# R7FS5D37A3A01CFM.net
KiCad netlist of a schematic drawn in EAGLE
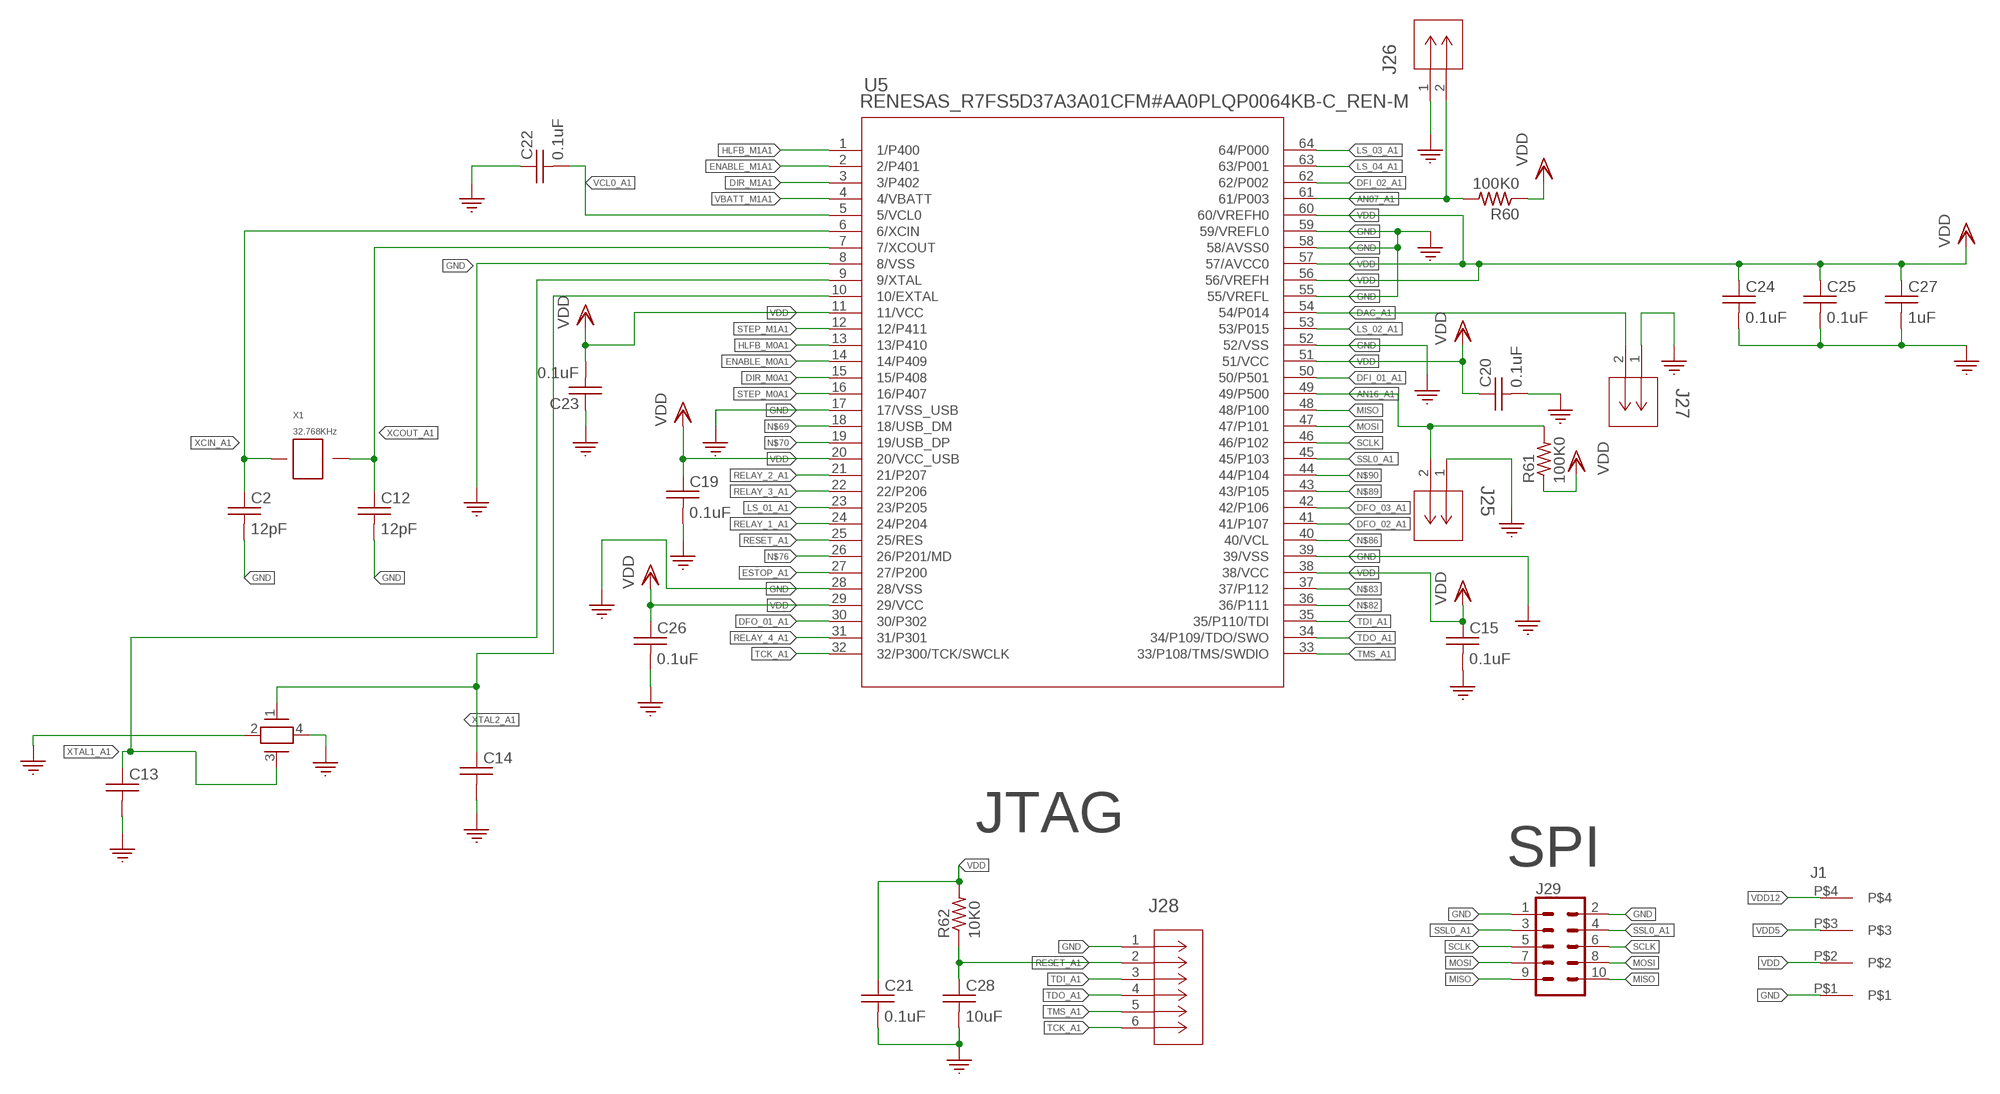
[diagram p0: schematic, sheet 1, part 1 of 3]
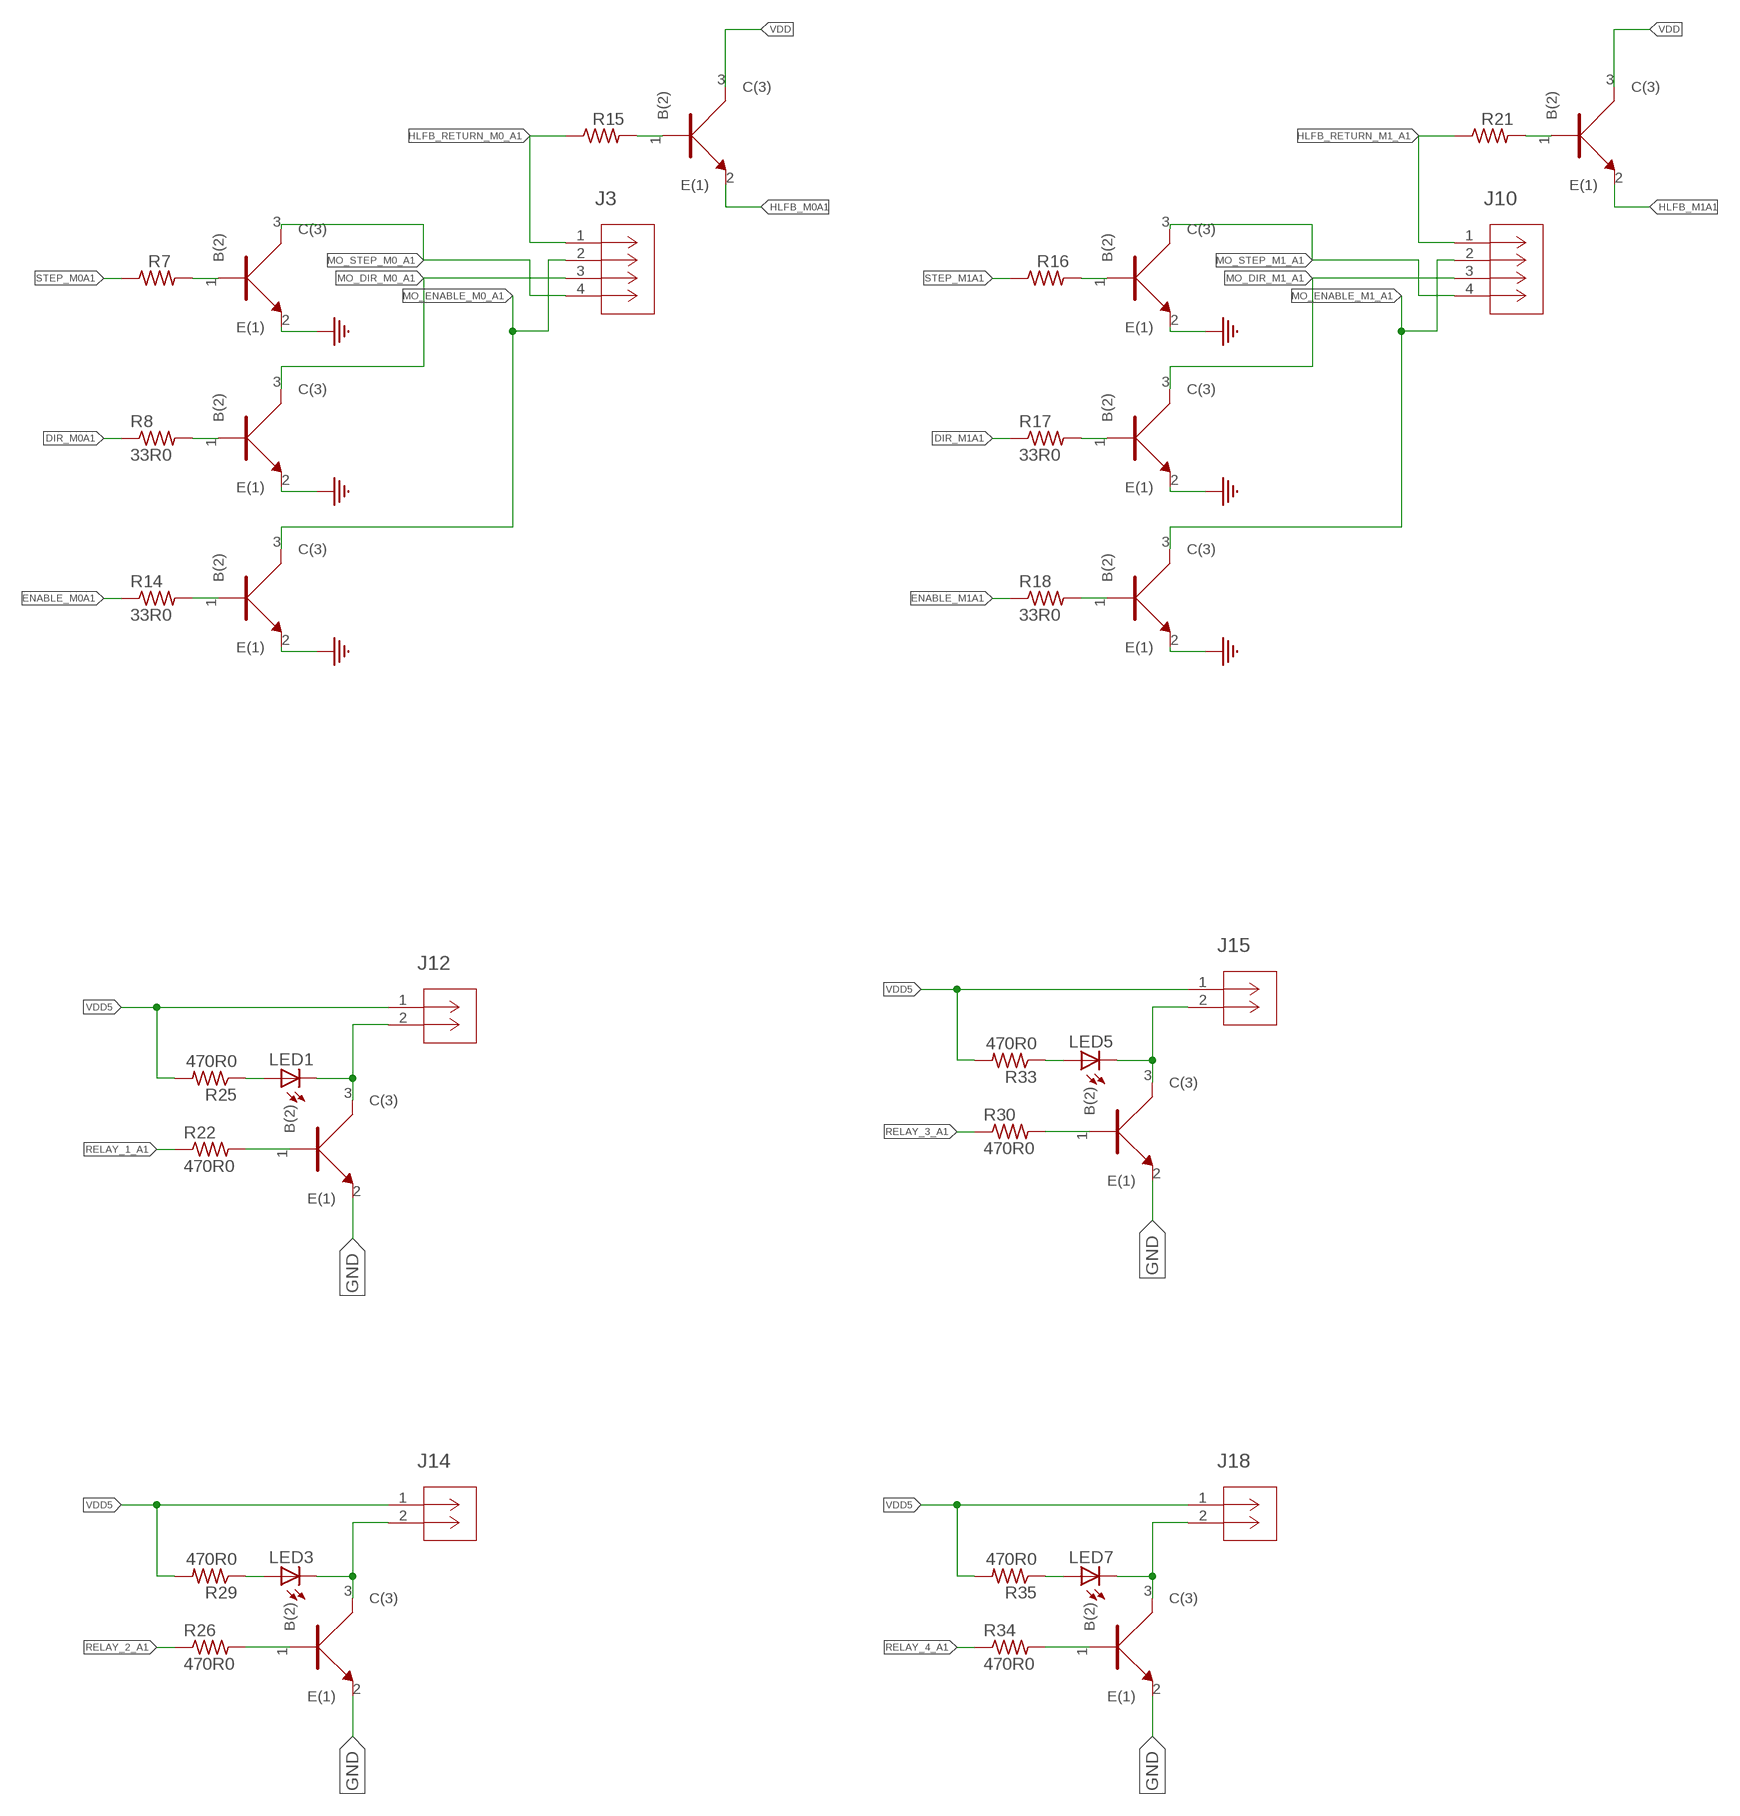
[diagram p1: schematic, sheet 1, part 2 of 3]
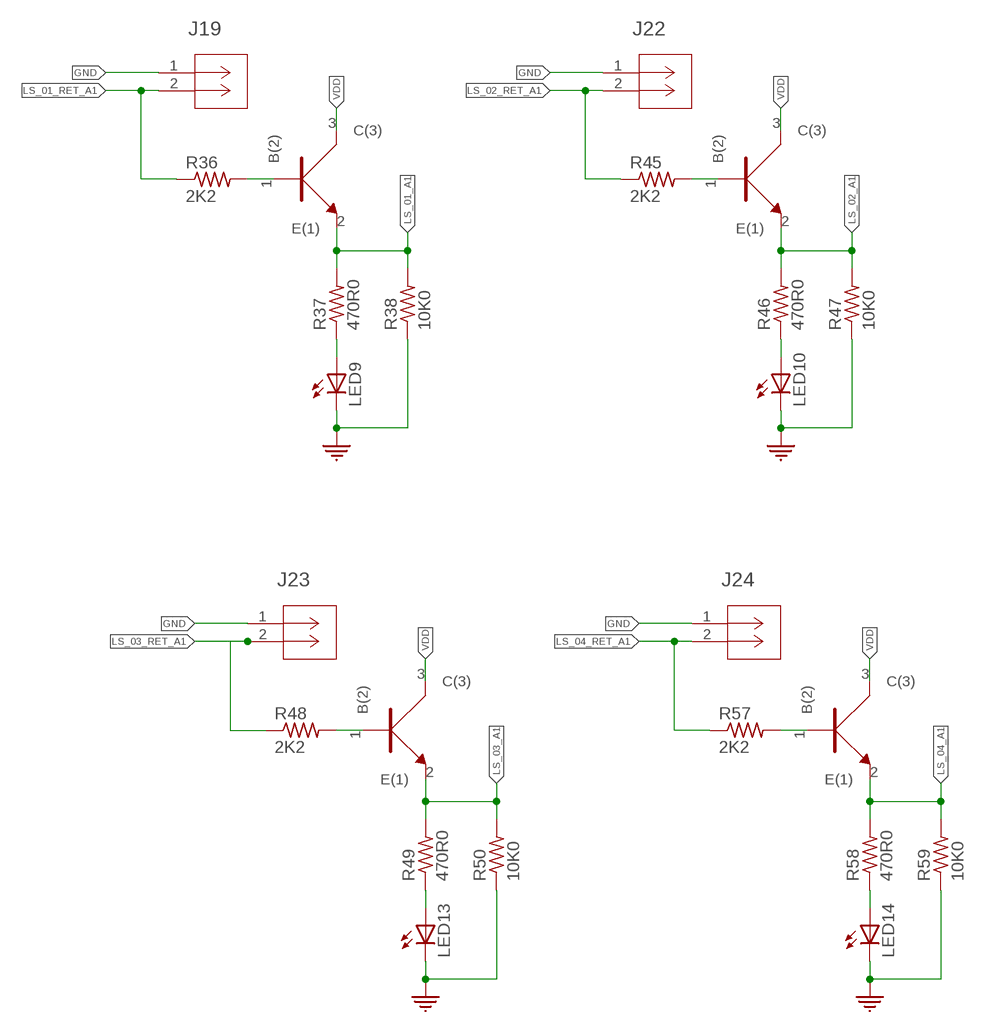
[diagram p2: schematic, sheet 1, part 3 of 3]

(export (version "E")
  (design (tool "Eeschema 10.0.6"))
  (components
    (comp (ref "C2")
      (value "12pF")
      (footprint "eagle-import:0402")
      (fields (field (name "PARTNO") "CL05C120JB5NNNC"))
      (libsource (lib "eagle-import") (part "C_0402_12PF"))
    )
    (comp (ref "C12")
      (value "12pF")
      (footprint "eagle-import:0402")
      (fields (field (name "PARTNO") "CL05C120JB5NNNC"))
      (libsource (lib "eagle-import") (part "C_0402_12PF"))
    )
    (comp (ref "C13")
      (value "10pF")
      (footprint "eagle-import:0402")
      (fields (field (name "PARTNO") "CC0402JRNPO9BN100"))
      (libsource (lib "eagle-import") (part "C_0402_10PF"))
    )
    (comp (ref "C14")
      (value "10pF")
      (footprint "eagle-import:0402")
      (fields (field (name "PARTNO") "CC0402JRNPO9BN100"))
      (libsource (lib "eagle-import") (part "C_0402_10PF"))
    )
    (comp (ref "C15")
      (value "0.1uF")
      (footprint "eagle-import:0402")
      (fields (field (name "PARTNO") "CL05F104ZO5NNNC"))
      (libsource (lib "eagle-import") (part "C_0402_0.1UF"))
    )
    (comp (ref "C19")
      (value "0.1uF")
      (footprint "eagle-import:0402")
      (fields (field (name "PARTNO") "CL05F104ZO5NNNC"))
      (libsource (lib "eagle-import") (part "C_0402_0.1UF"))
    )
    (comp (ref "C20")
      (value "0.1uF")
      (footprint "eagle-import:0402")
      (fields (field (name "PARTNO") "CL05F104ZO5NNNC"))
      (libsource (lib "eagle-import") (part "C_0402_0.1UF"))
    )
    (comp (ref "C21")
      (value "0.1uF")
      (footprint "eagle-import:0402")
      (fields (field (name "PARTNO") "CL05F104ZO5NNNC"))
      (libsource (lib "eagle-import") (part "C_0402_0.1UF"))
    )
    (comp (ref "C22")
      (value "0.1uF")
      (footprint "eagle-import:0402")
      (fields (field (name "PARTNO") "CL05F104ZO5NNNC"))
      (libsource (lib "eagle-import") (part "C_0402_0.1UF"))
    )
    (comp (ref "C23")
      (value "0.1uF")
      (footprint "eagle-import:0402")
      (fields (field (name "PARTNO") "CL05F104ZO5NNNC"))
      (libsource (lib "eagle-import") (part "C_0402_0.1UF"))
    )
    (comp (ref "C24")
      (value "0.1uF")
      (footprint "eagle-import:0402")
      (fields (field (name "PARTNO") "CL05F104ZO5NNNC"))
      (libsource (lib "eagle-import") (part "C_0402_0.1UF"))
    )
    (comp (ref "C25")
      (value "0.1uF")
      (footprint "eagle-import:0402")
      (fields (field (name "PARTNO") "CL05F104ZO5NNNC"))
      (libsource (lib "eagle-import") (part "C_0402_0.1UF"))
    )
    (comp (ref "C26")
      (value "0.1uF")
      (footprint "eagle-import:0402")
      (fields (field (name "PARTNO") "CL05F104ZO5NNNC"))
      (libsource (lib "eagle-import") (part "C_0402_0.1UF"))
    )
    (comp (ref "C27")
      (value "1uF")
      (footprint "eagle-import:0402")
      (fields (field (name "PARTNO") "CL05A105KO5NNNC"))
      (libsource (lib "eagle-import") (part "C_0402_1UF"))
    )
    (comp (ref "C28")
      (value "10uF")
      (footprint "eagle-import:0402")
      (fields (field (name "PARTNO") "CL05A106MP8NUB8"))
      (libsource (lib "eagle-import") (part "C_0402_10UF"))
    )
    (comp (ref "J1")
      (value "4-pos")
      (footprint "eagle-import:1X4_3.81MM_PITCH")
      (fields (field (name "PARTNO") "691322310004"))
      (libsource (lib "eagle-import") (part "3.81MM_1_X_4_RT_ANGLE_PLUG_HEADER"))
    )
    (comp (ref "J3")
      (value "CONN_530470410_PICOBLADE_X_4")
      (footprint "eagle-import:CON_530470410_MOL")
      (fields
        (field (name "PARTNO") "530470410")
        (field (name "COPYRIGHT") "Copyright (C) 2022 Ultra Librarian. All rights reserved.")
      )
      (libsource (lib "eagle-import") (part "CONN_530470410_PICOBLADE_X_4"))
    )
    (comp (ref "J10")
      (value "CONN_530470410_PICOBLADE_X_4")
      (footprint "eagle-import:CON_530470410_MOL")
      (fields
        (field (name "PARTNO") "530470410")
        (field (name "COPYRIGHT") "Copyright (C) 2022 Ultra Librarian. All rights reserved.")
      )
      (libsource (lib "eagle-import") (part "CONN_530470410_PICOBLADE_X_4"))
    )
    (comp (ref "J12")
      (value "CONN_530470210_PICOBLADE_X_2")
      (footprint "eagle-import:CON_530470210_MOL")
      (fields (field (name "PARTNO") "530470210"))
      (libsource (lib "eagle-import") (part "CONN_530470210_PICOBLADE_X_2"))
    )
    (comp (ref "J14")
      (value "CONN_530470210_PICOBLADE_X_2")
      (footprint "eagle-import:CON_530470210_MOL")
      (fields (field (name "PARTNO") "530470210"))
      (libsource (lib "eagle-import") (part "CONN_530470210_PICOBLADE_X_2"))
    )
    (comp (ref "J15")
      (value "CONN_530470210_PICOBLADE_X_2")
      (footprint "eagle-import:CON_530470210_MOL")
      (fields (field (name "PARTNO") "530470210"))
      (libsource (lib "eagle-import") (part "CONN_530470210_PICOBLADE_X_2"))
    )
    (comp (ref "J18")
      (value "CONN_530470210_PICOBLADE_X_2")
      (footprint "eagle-import:CON_530470210_MOL")
      (fields (field (name "PARTNO") "530470210"))
      (libsource (lib "eagle-import") (part "CONN_530470210_PICOBLADE_X_2"))
    )
    (comp (ref "J19")
      (value "CONN_530470210_PICOBLADE_X_2")
      (footprint "eagle-import:CON_530470210_MOL")
      (fields (field (name "PARTNO") "530470210"))
      (libsource (lib "eagle-import") (part "CONN_530470210_PICOBLADE_X_2"))
    )
    (comp (ref "J22")
      (value "CONN_530470210_PICOBLADE_X_2")
      (footprint "eagle-import:CON_530470210_MOL")
      (fields (field (name "PARTNO") "530470210"))
      (libsource (lib "eagle-import") (part "CONN_530470210_PICOBLADE_X_2"))
    )
    (comp (ref "J23")
      (value "CONN_530470210_PICOBLADE_X_2")
      (footprint "eagle-import:CON_530470210_MOL")
      (fields (field (name "PARTNO") "530470210"))
      (libsource (lib "eagle-import") (part "CONN_530470210_PICOBLADE_X_2"))
    )
    (comp (ref "J24")
      (value "CONN_530470210_PICOBLADE_X_2")
      (footprint "eagle-import:CON_530470210_MOL")
      (fields (field (name "PARTNO") "530470210"))
      (libsource (lib "eagle-import") (part "CONN_530470210_PICOBLADE_X_2"))
    )
    (comp (ref "J25")
      (value "CONN_530470210_PICOBLADE_X_2")
      (footprint "eagle-import:CON_530470210_MOL")
      (fields (field (name "PARTNO") "530470210"))
      (libsource (lib "eagle-import") (part "CONN_530470210_PICOBLADE_X_2"))
    )
    (comp (ref "J26")
      (value "CONN_530470210_PICOBLADE_X_2")
      (footprint "eagle-import:CON_530470210_MOL")
      (fields (field (name "PARTNO") "530470210"))
      (libsource (lib "eagle-import") (part "CONN_530470210_PICOBLADE_X_2"))
    )
    (comp (ref "J27")
      (value "CONN_530470210_PICOBLADE_X_2")
      (footprint "eagle-import:CON_530470210_MOL")
      (fields (field (name "PARTNO") "530470210"))
      (libsource (lib "eagle-import") (part "CONN_530470210_PICOBLADE_X_2"))
    )
    (comp (ref "J28")
      (value "CONN_530470610_PICOBLADE_X_6")
      (footprint "eagle-import:CON_530470610_MOL")
      (fields
        (field (name "PARTNO") "530470610")
        (field (name "COPYRIGHT") "Copyright (C) 2023 Ultra Librarian. All rights reserved.")
      )
      (libsource (lib "eagle-import") (part "CONN_530470610_PICOBLADE_X_6"))
    )
    (comp (ref "J29")
      (value "CONN_05X2PTH")
      (footprint "eagle-import:2X5")
      (libsource (lib "eagle-import") (part "CONN_05X2PTH"))
    )
    (comp (ref "LED1")
      (value "Green")
      (footprint "eagle-import:0805")
      (fields (field (name "PARTNO") "LG R971-KN-1"))
      (libsource (lib "eagle-import") (part "LED_0805_GREEN"))
    )
    (comp (ref "LED3")
      (value "Green")
      (footprint "eagle-import:0805")
      (fields (field (name "PARTNO") "LG R971-KN-1"))
      (libsource (lib "eagle-import") (part "LED_0805_GREEN"))
    )
    (comp (ref "LED5")
      (value "Green")
      (footprint "eagle-import:0805")
      (fields (field (name "PARTNO") "LG R971-KN-1"))
      (libsource (lib "eagle-import") (part "LED_0805_GREEN"))
    )
    (comp (ref "LED7")
      (value "Green")
      (footprint "eagle-import:0805")
      (fields (field (name "PARTNO") "LG R971-KN-1"))
      (libsource (lib "eagle-import") (part "LED_0805_GREEN"))
    )
    (comp (ref "LED9")
      (value "Green")
      (footprint "eagle-import:0805")
      (fields (field (name "PARTNO") "LG R971-KN-1"))
      (libsource (lib "eagle-import") (part "LED_0805_GREEN"))
    )
    (comp (ref "LED10")
      (value "Green")
      (footprint "eagle-import:0805")
      (fields (field (name "PARTNO") "LG R971-KN-1"))
      (libsource (lib "eagle-import") (part "LED_0805_GREEN"))
    )
    (comp (ref "LED13")
      (value "Green")
      (footprint "eagle-import:0805")
      (fields (field (name "PARTNO") "LG R971-KN-1"))
      (libsource (lib "eagle-import") (part "LED_0805_GREEN"))
    )
    (comp (ref "LED14")
      (value "Green")
      (footprint "eagle-import:0805")
      (fields (field (name "PARTNO") "LG R971-KN-1"))
      (libsource (lib "eagle-import") (part "LED_0805_GREEN"))
    )
    (comp (ref "R7")
      (value "33R0")
      (footprint "eagle-import:0402")
      (fields (field (name "PARTNO") "RMCF0402JT33R0"))
      (libsource (lib "eagle-import") (part "R_0402_33R0"))
    )
    (comp (ref "R8")
      (value "33R0")
      (footprint "eagle-import:0402")
      (fields (field (name "PARTNO") "RMCF0402JT33R0"))
      (libsource (lib "eagle-import") (part "R_0402_33R0"))
    )
    (comp (ref "R14")
      (value "33R0")
      (footprint "eagle-import:0402")
      (fields (field (name "PARTNO") "RMCF0402JT33R0"))
      (libsource (lib "eagle-import") (part "R_0402_33R0"))
    )
    (comp (ref "R15")
      (value "33R0")
      (footprint "eagle-import:0402")
      (fields (field (name "PARTNO") "RMCF0402JT33R0"))
      (libsource (lib "eagle-import") (part "R_0402_33R0"))
    )
    (comp (ref "R16")
      (value "33R0")
      (footprint "eagle-import:0402")
      (fields (field (name "PARTNO") "RMCF0402JT33R0"))
      (libsource (lib "eagle-import") (part "R_0402_33R0"))
    )
    (comp (ref "R17")
      (value "33R0")
      (footprint "eagle-import:0402")
      (fields (field (name "PARTNO") "RMCF0402JT33R0"))
      (libsource (lib "eagle-import") (part "R_0402_33R0"))
    )
    (comp (ref "R18")
      (value "33R0")
      (footprint "eagle-import:0402")
      (fields (field (name "PARTNO") "RMCF0402JT33R0"))
      (libsource (lib "eagle-import") (part "R_0402_33R0"))
    )
    (comp (ref "R21")
      (value "33R0")
      (footprint "eagle-import:0402")
      (fields (field (name "PARTNO") "RMCF0402JT33R0"))
      (libsource (lib "eagle-import") (part "R_0402_33R0"))
    )
    (comp (ref "R22")
      (value "470R0")
      (footprint "eagle-import:0402")
      (fields (field (name "PARTNO") "RMCF0402JT470R"))
      (libsource (lib "eagle-import") (part "R_0402_470R0"))
    )
    (comp (ref "R25")
      (value "470R0")
      (footprint "eagle-import:0402")
      (fields (field (name "PARTNO") "RMCF0402JT470R"))
      (libsource (lib "eagle-import") (part "R_0402_470R0"))
    )
    (comp (ref "R26")
      (value "470R0")
      (footprint "eagle-import:0402")
      (fields (field (name "PARTNO") "RMCF0402JT470R"))
      (libsource (lib "eagle-import") (part "R_0402_470R0"))
    )
    (comp (ref "R29")
      (value "470R0")
      (footprint "eagle-import:0402")
      (fields (field (name "PARTNO") "RMCF0402JT470R"))
      (libsource (lib "eagle-import") (part "R_0402_470R0"))
    )
    (comp (ref "R30")
      (value "470R0")
      (footprint "eagle-import:0402")
      (fields (field (name "PARTNO") "RMCF0402JT470R"))
      (libsource (lib "eagle-import") (part "R_0402_470R0"))
    )
    (comp (ref "R33")
      (value "470R0")
      (footprint "eagle-import:0402")
      (fields (field (name "PARTNO") "RMCF0402JT470R"))
      (libsource (lib "eagle-import") (part "R_0402_470R0"))
    )
    (comp (ref "R34")
      (value "470R0")
      (footprint "eagle-import:0402")
      (fields (field (name "PARTNO") "RMCF0402JT470R"))
      (libsource (lib "eagle-import") (part "R_0402_470R0"))
    )
    (comp (ref "R35")
      (value "470R0")
      (footprint "eagle-import:0402")
      (fields (field (name "PARTNO") "RMCF0402JT470R"))
      (libsource (lib "eagle-import") (part "R_0402_470R0"))
    )
    (comp (ref "R36")
      (value "2K2")
      (footprint "eagle-import:0402")
      (fields (field (name "PARTNO") "RMCF0402JT2K20"))
      (libsource (lib "eagle-import") (part "R_0402_2K2"))
    )
    (comp (ref "R37")
      (value "470R0")
      (footprint "eagle-import:0402")
      (fields (field (name "PARTNO") "RMCF0402JT470R"))
      (libsource (lib "eagle-import") (part "R_0402_470R0"))
    )
    (comp (ref "R38")
      (value "10K0")
      (footprint "eagle-import:0402")
      (fields (field (name "PARTNO") "RMCF0402JT10K0"))
      (libsource (lib "eagle-import") (part "R_0402_10K0"))
    )
    (comp (ref "R45")
      (value "2K2")
      (footprint "eagle-import:0402")
      (fields (field (name "PARTNO") "RMCF0402JT2K20"))
      (libsource (lib "eagle-import") (part "R_0402_2K2"))
    )
    (comp (ref "R46")
      (value "470R0")
      (footprint "eagle-import:0402")
      (fields (field (name "PARTNO") "RMCF0402JT470R"))
      (libsource (lib "eagle-import") (part "R_0402_470R0"))
    )
    (comp (ref "R47")
      (value "10K0")
      (footprint "eagle-import:0402")
      (fields (field (name "PARTNO") "RMCF0402JT10K0"))
      (libsource (lib "eagle-import") (part "R_0402_10K0"))
    )
    (comp (ref "R48")
      (value "2K2")
      (footprint "eagle-import:0402")
      (fields (field (name "PARTNO") "RMCF0402JT2K20"))
      (libsource (lib "eagle-import") (part "R_0402_2K2"))
    )
    (comp (ref "R49")
      (value "470R0")
      (footprint "eagle-import:0402")
      (fields (field (name "PARTNO") "RMCF0402JT470R"))
      (libsource (lib "eagle-import") (part "R_0402_470R0"))
    )
    (comp (ref "R50")
      (value "10K0")
      (footprint "eagle-import:0402")
      (fields (field (name "PARTNO") "RMCF0402JT10K0"))
      (libsource (lib "eagle-import") (part "R_0402_10K0"))
    )
    (comp (ref "R57")
      (value "2K2")
      (footprint "eagle-import:0402")
      (fields (field (name "PARTNO") "RMCF0402JT2K20"))
      (libsource (lib "eagle-import") (part "R_0402_2K2"))
    )
    (comp (ref "R58")
      (value "470R0")
      (footprint "eagle-import:0402")
      (fields (field (name "PARTNO") "RMCF0402JT470R"))
      (libsource (lib "eagle-import") (part "R_0402_470R0"))
    )
    (comp (ref "R59")
      (value "10K0")
      (footprint "eagle-import:0402")
      (fields (field (name "PARTNO") "RMCF0402JT10K0"))
      (libsource (lib "eagle-import") (part "R_0402_10K0"))
    )
    (comp (ref "R60")
      (value "100K0")
      (footprint "eagle-import:0402")
      (fields (field (name "PARTNO") "RCG0402100KFKED"))
      (libsource (lib "eagle-import") (part "R_0402_100K0"))
    )
    (comp (ref "R61")
      (value "100K0")
      (footprint "eagle-import:0402")
      (fields (field (name "PARTNO") "RCG0402100KFKED"))
      (libsource (lib "eagle-import") (part "R_0402_100K0"))
    )
    (comp (ref "R62")
      (value "10K0")
      (footprint "eagle-import:0402")
      (fields (field (name "PARTNO") "RMCF0402JT10K0"))
      (libsource (lib "eagle-import") (part "R_0402_10K0"))
    )
    (comp (ref "U5")
      (value "RENESAS_R7FS5D37A3A01CFM#AA0PLQP0064KB-C_REN-M")
      (footprint "eagle-import:PLQP0064KB-C_REN-M")
      (fields
        (field (name "PARTNO") "R7FS3A37A3A01CFM#AA0")
        (field (name "COPYRIGHT") "Copyright (C) 2023 Ultra Librarian. All rights reserved.")
      )
      (libsource (lib "eagle-import") (part "RENESAS_R7FS5D37A3A01CFM#AA0PLQP0064KB-C_REN-M"))
    )
    (comp (ref "U6")
      (value "NPN")
      (footprint "eagle-import:SOT323")
      (fields (field (name "PARTNO") "BC846BW_NPN"))
      (libsource (lib "eagle-import") (part "BC846BW"))
    )
    (comp (ref "U7")
      (value "NPN")
      (footprint "eagle-import:SOT323")
      (fields (field (name "PARTNO") "BC846BW_NPN"))
      (libsource (lib "eagle-import") (part "BC846BW"))
    )
    (comp (ref "U8")
      (value "NPN")
      (footprint "eagle-import:SOT323")
      (fields (field (name "PARTNO") "BC846BW_NPN"))
      (libsource (lib "eagle-import") (part "BC846BW"))
    )
    (comp (ref "U13")
      (value "NPN")
      (footprint "eagle-import:SOT323")
      (fields (field (name "PARTNO") "BC846BW_NPN"))
      (libsource (lib "eagle-import") (part "BC846BW"))
    )
    (comp (ref "U14")
      (value "NPN")
      (footprint "eagle-import:SOT323")
      (fields (field (name "PARTNO") "BC846BW_NPN"))
      (libsource (lib "eagle-import") (part "BC846BW"))
    )
    (comp (ref "U15")
      (value "NPN")
      (footprint "eagle-import:SOT323")
      (fields (field (name "PARTNO") "BC846BW_NPN"))
      (libsource (lib "eagle-import") (part "BC846BW"))
    )
    (comp (ref "U16")
      (value "NPN")
      (footprint "eagle-import:SOT323")
      (fields (field (name "PARTNO") "BC846BW_NPN"))
      (libsource (lib "eagle-import") (part "BC846BW"))
    )
    (comp (ref "U18")
      (value "NPN")
      (footprint "eagle-import:SOT323")
      (fields (field (name "PARTNO") "BC846BW_NPN"))
      (libsource (lib "eagle-import") (part "BC846BW"))
    )
    (comp (ref "U20")
      (value "NPN")
      (footprint "eagle-import:SOT323")
      (fields (field (name "PARTNO") "BC846BW_NPN"))
      (libsource (lib "eagle-import") (part "BC846BW"))
    )
    (comp (ref "U22")
      (value "NPN")
      (footprint "eagle-import:SOT323")
      (fields (field (name "PARTNO") "BC846BW_NPN"))
      (libsource (lib "eagle-import") (part "BC846BW"))
    )
    (comp (ref "U24")
      (value "NPN")
      (footprint "eagle-import:SOT323")
      (fields (field (name "PARTNO") "BC846BW_NPN"))
      (libsource (lib "eagle-import") (part "BC846BW"))
    )
    (comp (ref "U26")
      (value "NPN")
      (footprint "eagle-import:SOT323")
      (fields (field (name "PARTNO") "BC846BW_NPN"))
      (libsource (lib "eagle-import") (part "BC846BW"))
    )
    (comp (ref "U27")
      (value "NPN")
      (footprint "eagle-import:SOT323")
      (fields (field (name "PARTNO") "BC846BW_NPN"))
      (libsource (lib "eagle-import") (part "BC846BW"))
    )
    (comp (ref "U30")
      (value "NPN")
      (footprint "eagle-import:SOT323")
      (fields (field (name "PARTNO") "BC846BW_NPN"))
      (libsource (lib "eagle-import") (part "BC846BW"))
    )
    (comp (ref "U31")
      (value "NPN")
      (footprint "eagle-import:SOT323")
      (fields (field (name "PARTNO") "BC846BW_NPN"))
      (libsource (lib "eagle-import") (part "BC846BW"))
    )
    (comp (ref "U34")
      (value "NPN")
      (footprint "eagle-import:SOT323")
      (fields (field (name "PARTNO") "BC846BW_NPN"))
      (libsource (lib "eagle-import") (part "BC846BW"))
    )
    (comp (ref "X1")
      (value "32.768KHz")
      (footprint "eagle-import:SMD_X_2_PADS")
      (fields (field (name "PARTNO") "ABS07-32.768KHZ-T"))
      (libsource (lib "eagle-import") (part "XTAL_32.768KHZ"))
    )
    (comp (ref "Y2")
      (value "XTAL_12MHZ_ABM8G-12.000MHZ-B4Y-T")
      (footprint "eagle-import:CRYSTAL_ABM8G_ABR")
      (fields
        (field (name "PARTNO") "ABM8G-12.000MHZ-B4Y-T")
        (field (name "COPYRIGHT") "Copyright (C) 2023 Ultra Librarian. All rights reserved.")
      )
      (libsource (lib "eagle-import") (part "XTAL_12MHZ_ABM8G-12.000MHZ-B4Y-T"))
    )
  )
  (nets
    (net (code "1") (name "AN07_A1") (class "Default")
      (node (ref "J26") (pin "2") (pinfunction "2_2") (pintype "passive"))
      (node (ref "R60") (pin "P$2") (pinfunction "2_P$2") (pintype "passive"))
      (node (ref "U5") (pin "61") (pinfunction "61/P003_61") (pintype "bidirectional"))
    )
    (net (code "2") (name "AN16_A1") (class "Default")
      (node (ref "J25") (pin "2") (pinfunction "2_2") (pintype "passive"))
      (node (ref "R61") (pin "P$2") (pinfunction "2_P$2") (pintype "passive"))
      (node (ref "U5") (pin "49") (pinfunction "49/P500_49") (pintype "bidirectional"))
    )
    (net (code "3") (name "DAC_A1") (class "Default")
      (node (ref "J27") (pin "2") (pinfunction "2_2") (pintype "passive"))
      (node (ref "U5") (pin "54") (pinfunction "54/P014_54") (pintype "bidirectional"))
    )
    (net (code "4") (name "DFI_01_A1") (class "Default")
      (node (ref "U5") (pin "50") (pinfunction "50/P501_50") (pintype "bidirectional"))
    )
    (net (code "5") (name "DFI_02_A1") (class "Default")
      (node (ref "U5") (pin "62") (pinfunction "62/P002_62") (pintype "bidirectional"))
    )
    (net (code "6") (name "DFO_01_A1") (class "Default")
      (node (ref "U5") (pin "30") (pinfunction "30/P302_30") (pintype "bidirectional"))
    )
    (net (code "7") (name "DFO_02_A1") (class "Default")
      (node (ref "U5") (pin "41") (pinfunction "41/P107_41") (pintype "bidirectional"))
    )
    (net (code "8") (name "DFO_03_A1") (class "Default")
      (node (ref "U5") (pin "42") (pinfunction "42/P106_42") (pintype "bidirectional"))
    )
    (net (code "9") (name "DIR_M0A1") (class "Default")
      (node (ref "R8") (pin "P$1") (pinfunction "1_P$1") (pintype "passive"))
      (node (ref "U5") (pin "15") (pinfunction "15/P408_15") (pintype "bidirectional"))
    )
    (net (code "10") (name "DIR_M1A1") (class "Default")
      (node (ref "R17") (pin "P$1") (pinfunction "1_P$1") (pintype "passive"))
      (node (ref "U5") (pin "3") (pinfunction "3/P402_3") (pintype "bidirectional"))
    )
    (net (code "11") (name "ENABLE_M0A1") (class "Default")
      (node (ref "R14") (pin "P$1") (pinfunction "1_P$1") (pintype "passive"))
      (node (ref "U5") (pin "14") (pinfunction "14/P409_14") (pintype "bidirectional"))
    )
    (net (code "12") (name "ENABLE_M1A1") (class "Default")
      (node (ref "R18") (pin "P$1") (pinfunction "1_P$1") (pintype "passive"))
      (node (ref "U5") (pin "2") (pinfunction "2/P401_2") (pintype "bidirectional"))
    )
    (net (code "13") (name "ESTOP_A1") (class "Default")
      (node (ref "U5") (pin "27") (pinfunction "27/P200_27") (pintype "bidirectional"))
    )
    (net (code "14") (name "GND") (class "Default")
      (node (ref "C12") (pin "P$2") (pinfunction "2_P$2") (pintype "passive"))
      (node (ref "C13") (pin "P$2") (pinfunction "2_P$2") (pintype "passive"))
      (node (ref "C14") (pin "P$2") (pinfunction "2_P$2") (pintype "passive"))
      (node (ref "C15") (pin "P$2") (pinfunction "2_P$2") (pintype "passive"))
      (node (ref "C19") (pin "P$2") (pinfunction "2_P$2") (pintype "passive"))
      (node (ref "C2") (pin "P$2") (pinfunction "2_P$2") (pintype "passive"))
      (node (ref "C20") (pin "P$2") (pinfunction "2_P$2") (pintype "passive"))
      (node (ref "C21") (pin "P$2") (pinfunction "2_P$2") (pintype "passive"))
      (node (ref "C22") (pin "P$1") (pinfunction "1_P$1") (pintype "passive"))
      (node (ref "C23") (pin "P$1") (pinfunction "1_P$1") (pintype "passive"))
      (node (ref "C24") (pin "P$2") (pinfunction "2_P$2") (pintype "passive"))
      (node (ref "C25") (pin "P$2") (pinfunction "2_P$2") (pintype "passive"))
      (node (ref "C26") (pin "P$2") (pinfunction "2_P$2") (pintype "passive"))
      (node (ref "C27") (pin "P$2") (pinfunction "2_P$2") (pintype "passive"))
      (node (ref "C28") (pin "P$2") (pinfunction "2_P$2") (pintype "passive"))
      (node (ref "J1") (pin "P$1") (pinfunction "P$1_P$1") (pintype "bidirectional"))
      (node (ref "J19") (pin "1") (pinfunction "1_1") (pintype "passive"))
      (node (ref "J22") (pin "1") (pinfunction "1_1") (pintype "passive"))
      (node (ref "J23") (pin "1") (pinfunction "1_1") (pintype "passive"))
      (node (ref "J24") (pin "1") (pinfunction "1_1") (pintype "passive"))
      (node (ref "J25") (pin "1") (pinfunction "1_1") (pintype "passive"))
      (node (ref "J26") (pin "1") (pinfunction "1_1") (pintype "passive"))
      (node (ref "J27") (pin "1") (pinfunction "1_1") (pintype "passive"))
      (node (ref "J28") (pin "1") (pinfunction "1_1") (pintype "passive"))
      (node (ref "J29") (pin "1") (pinfunction "1_1") (pintype "passive"))
      (node (ref "J29") (pin "2") (pinfunction "2_2") (pintype "passive"))
      (node (ref "LED10") (pin "2") (pinfunction "C_2") (pintype "passive"))
      (node (ref "LED13") (pin "2") (pinfunction "C_2") (pintype "passive"))
      (node (ref "LED14") (pin "2") (pinfunction "C_2") (pintype "passive"))
      (node (ref "LED9") (pin "2") (pinfunction "C_2") (pintype "passive"))
      (node (ref "R38") (pin "P$1") (pinfunction "1_P$1") (pintype "passive"))
      (node (ref "R47") (pin "P$1") (pinfunction "1_P$1") (pintype "passive"))
      (node (ref "R50") (pin "P$1") (pinfunction "1_P$1") (pintype "passive"))
      (node (ref "R59") (pin "P$1") (pinfunction "1_P$1") (pintype "passive"))
      (node (ref "U14") (pin "2") (pinfunction "E(1)_2") (pintype "output"))
      (node (ref "U15") (pin "2") (pinfunction "E(1)_2") (pintype "output"))
      (node (ref "U16") (pin "2") (pinfunction "E(1)_2") (pintype "output"))
      (node (ref "U20") (pin "2") (pinfunction "E(1)_2") (pintype "output"))
      (node (ref "U22") (pin "2") (pinfunction "E(1)_2") (pintype "output"))
      (node (ref "U24") (pin "2") (pinfunction "E(1)_2") (pintype "output"))
      (node (ref "U26") (pin "2") (pinfunction "E(1)_2") (pintype "output"))
      (node (ref "U5") (pin "17") (pinfunction "17/VSS_USB_17") (pintype "power_in"))
      (node (ref "U5") (pin "28") (pinfunction "28/VSS_28") (pintype "bidirectional"))
      (node (ref "U5") (pin "39") (pinfunction "39/VSS_39") (pintype "power_in"))
      (node (ref "U5") (pin "52") (pinfunction "52/VSS_52") (pintype "bidirectional"))
      (node (ref "U5") (pin "55") (pinfunction "55/VREFL_55") (pintype "bidirectional"))
      (node (ref "U5") (pin "58") (pinfunction "58/AVSS0_58") (pintype "bidirectional"))
      (node (ref "U5") (pin "59") (pinfunction "59/VREFL0_59") (pintype "bidirectional"))
      (node (ref "U5") (pin "8") (pinfunction "8/VSS_8") (pintype "power_in"))
      (node (ref "U6") (pin "2") (pinfunction "E(1)_2") (pintype "output"))
      (node (ref "U7") (pin "2") (pinfunction "E(1)_2") (pintype "output"))
      (node (ref "U8") (pin "2") (pinfunction "E(1)_2") (pintype "output"))
      (node (ref "Y2") (pin "2") (pinfunction "2_2") (pintype "passive"))
      (node (ref "Y2") (pin "4") (pinfunction "4_4") (pintype "passive"))
    )
    (net (code "15") (name "HLFB_M0A1") (class "Default")
      (node (ref "U13") (pin "2") (pinfunction "E(1)_2") (pintype "output"))
      (node (ref "U5") (pin "13") (pinfunction "13/P410_13") (pintype "bidirectional"))
    )
    (net (code "16") (name "HLFB_M1A1") (class "Default")
      (node (ref "U18") (pin "2") (pinfunction "E(1)_2") (pintype "output"))
      (node (ref "U5") (pin "1") (pinfunction "1/P400_1") (pintype "bidirectional"))
    )
    (net (code "17") (name "HLFB_RETURN_M0_A1") (class "Default")
      (node (ref "J3") (pin "1") (pinfunction "1_1") (pintype "passive"))
      (node (ref "R15") (pin "P$1") (pinfunction "1_P$1") (pintype "passive"))
    )
    (net (code "18") (name "HLFB_RETURN_M1_A1") (class "Default")
      (node (ref "J10") (pin "1") (pinfunction "1_1") (pintype "passive"))
      (node (ref "R21") (pin "P$1") (pinfunction "1_P$1") (pintype "passive"))
    )
    (net (code "19") (name "LS_01_A1") (class "Default")
      (node (ref "R37") (pin "P$2") (pinfunction "2_P$2") (pintype "passive"))
      (node (ref "R38") (pin "P$2") (pinfunction "2_P$2") (pintype "passive"))
      (node (ref "U27") (pin "2") (pinfunction "E(1)_2") (pintype "output"))
      (node (ref "U5") (pin "23") (pinfunction "23/P205_23") (pintype "bidirectional"))
    )
    (net (code "20") (name "LS_01_RET_A1") (class "Default")
      (node (ref "J19") (pin "2") (pinfunction "2_2") (pintype "passive"))
      (node (ref "R36") (pin "P$1") (pinfunction "1_P$1") (pintype "passive"))
    )
    (net (code "21") (name "LS_02_A1") (class "Default")
      (node (ref "R46") (pin "P$2") (pinfunction "2_P$2") (pintype "passive"))
      (node (ref "R47") (pin "P$2") (pinfunction "2_P$2") (pintype "passive"))
      (node (ref "U30") (pin "2") (pinfunction "E(1)_2") (pintype "output"))
      (node (ref "U5") (pin "53") (pinfunction "53/P015_53") (pintype "bidirectional"))
    )
    (net (code "22") (name "LS_02_RET_A1") (class "Default")
      (node (ref "J22") (pin "2") (pinfunction "2_2") (pintype "passive"))
      (node (ref "R45") (pin "P$1") (pinfunction "1_P$1") (pintype "passive"))
    )
    (net (code "23") (name "LS_03_A1") (class "Default")
      (node (ref "R49") (pin "P$2") (pinfunction "2_P$2") (pintype "passive"))
      (node (ref "R50") (pin "P$2") (pinfunction "2_P$2") (pintype "passive"))
      (node (ref "U31") (pin "2") (pinfunction "E(1)_2") (pintype "output"))
      (node (ref "U5") (pin "64") (pinfunction "64/P000_64") (pintype "bidirectional"))
    )
    (net (code "24") (name "LS_03_RET_A1") (class "Default")
      (node (ref "J23") (pin "2") (pinfunction "2_2") (pintype "passive"))
      (node (ref "R48") (pin "P$1") (pinfunction "1_P$1") (pintype "passive"))
    )
    (net (code "25") (name "LS_04_A1") (class "Default")
      (node (ref "R58") (pin "P$2") (pinfunction "2_P$2") (pintype "passive"))
      (node (ref "R59") (pin "P$2") (pinfunction "2_P$2") (pintype "passive"))
      (node (ref "U34") (pin "2") (pinfunction "E(1)_2") (pintype "output"))
      (node (ref "U5") (pin "63") (pinfunction "63/P001_63") (pintype "bidirectional"))
    )
    (net (code "26") (name "LS_04_RET_A1") (class "Default")
      (node (ref "J24") (pin "2") (pinfunction "2_2") (pintype "passive"))
      (node (ref "R57") (pin "P$1") (pinfunction "1_P$1") (pintype "passive"))
    )
    (net (code "27") (name "MISO") (class "Default")
      (node (ref "J29") (pin "10") (pinfunction "10_10") (pintype "passive"))
      (node (ref "J29") (pin "9") (pinfunction "9_9") (pintype "passive"))
      (node (ref "U5") (pin "48") (pinfunction "48/P100_48") (pintype "bidirectional"))
    )
    (net (code "28") (name "MOSI") (class "Default")
      (node (ref "J29") (pin "7") (pinfunction "7_7") (pintype "passive"))
      (node (ref "J29") (pin "8") (pinfunction "8_8") (pintype "passive"))
      (node (ref "U5") (pin "47") (pinfunction "47/P101_47") (pintype "bidirectional"))
    )
    (net (code "29") (name "MO_DIR_M0_A1") (class "Default")
      (node (ref "J3") (pin "3") (pinfunction "3_3") (pintype "passive"))
      (node (ref "U7") (pin "3") (pinfunction "C(3)_3") (pintype "input"))
    )
    (net (code "30") (name "MO_DIR_M1_A1") (class "Default")
      (node (ref "J10") (pin "3") (pinfunction "3_3") (pintype "passive"))
      (node (ref "U15") (pin "3") (pinfunction "C(3)_3") (pintype "input"))
    )
    (net (code "31") (name "MO_ENABLE_M0_A1") (class "Default")
      (node (ref "J3") (pin "2") (pinfunction "2_2") (pintype "passive"))
      (node (ref "U8") (pin "3") (pinfunction "C(3)_3") (pintype "input"))
    )
    (net (code "32") (name "MO_ENABLE_M1_A1") (class "Default")
      (node (ref "J10") (pin "2") (pinfunction "2_2") (pintype "passive"))
      (node (ref "U16") (pin "3") (pinfunction "C(3)_3") (pintype "input"))
    )
    (net (code "33") (name "MO_STEP_M0_A1") (class "Default")
      (node (ref "J3") (pin "4") (pinfunction "4_4") (pintype "passive"))
      (node (ref "U6") (pin "3") (pinfunction "C(3)_3") (pintype "input"))
    )
    (net (code "34") (name "MO_STEP_M1_A1") (class "Default")
      (node (ref "J10") (pin "4") (pinfunction "4_4") (pintype "passive"))
      (node (ref "U14") (pin "3") (pinfunction "C(3)_3") (pintype "input"))
    )
    (net (code "35") (name "N$69") (class "Default")
      (node (ref "U5") (pin "18") (pinfunction "18/USB_DM_18") (pintype "bidirectional"))
    )
    (net (code "36") (name "N$70") (class "Default")
      (node (ref "U5") (pin "19") (pinfunction "19/USB_DP_19") (pintype "bidirectional"))
    )
    (net (code "37") (name "N$76") (class "Default")
      (node (ref "U5") (pin "26") (pinfunction "26/P201/MD_26") (pintype "bidirectional"))
    )
    (net (code "38") (name "N$82") (class "Default")
      (node (ref "U5") (pin "36") (pinfunction "36/P111_36") (pintype "bidirectional"))
    )
    (net (code "39") (name "N$83") (class "Default")
      (node (ref "U5") (pin "37") (pinfunction "37/P112_37") (pintype "bidirectional"))
    )
    (net (code "40") (name "N$86") (class "Default")
      (node (ref "U5") (pin "40") (pinfunction "40/VCL_40") (pintype "power_in"))
    )
    (net (code "41") (name "N$89") (class "Default")
      (node (ref "U5") (pin "43") (pinfunction "43/P105_43") (pintype "bidirectional"))
    )
    (net (code "42") (name "N$90") (class "Default")
      (node (ref "U5") (pin "44") (pinfunction "44/P104_44") (pintype "bidirectional"))
    )
    (net (code "43") (name "Net-(LED1-A)") (class "Default")
      (node (ref "LED1") (pin "1") (pinfunction "A_1") (pintype "passive"))
      (node (ref "R25") (pin "P$1") (pinfunction "1_P$1") (pintype "passive"))
    )
    (net (code "44") (name "Net-(LED1-C)") (class "Default")
      (node (ref "J12") (pin "2") (pinfunction "2_2") (pintype "passive"))
      (node (ref "LED1") (pin "2") (pinfunction "C_2") (pintype "passive"))
      (node (ref "U20") (pin "3") (pinfunction "C(3)_3") (pintype "input"))
    )
    (net (code "45") (name "Net-(LED3-A)") (class "Default")
      (node (ref "LED3") (pin "1") (pinfunction "A_1") (pintype "passive"))
      (node (ref "R29") (pin "P$1") (pinfunction "1_P$1") (pintype "passive"))
    )
    (net (code "46") (name "Net-(LED3-C)") (class "Default")
      (node (ref "J14") (pin "2") (pinfunction "2_2") (pintype "passive"))
      (node (ref "LED3") (pin "2") (pinfunction "C_2") (pintype "passive"))
      (node (ref "U22") (pin "3") (pinfunction "C(3)_3") (pintype "input"))
    )
    (net (code "47") (name "Net-(LED5-A)") (class "Default")
      (node (ref "LED5") (pin "1") (pinfunction "A_1") (pintype "passive"))
      (node (ref "R33") (pin "P$1") (pinfunction "1_P$1") (pintype "passive"))
    )
    (net (code "48") (name "Net-(LED5-C)") (class "Default")
      (node (ref "J15") (pin "2") (pinfunction "2_2") (pintype "passive"))
      (node (ref "LED5") (pin "2") (pinfunction "C_2") (pintype "passive"))
      (node (ref "U24") (pin "3") (pinfunction "C(3)_3") (pintype "input"))
    )
    (net (code "49") (name "Net-(LED7-A)") (class "Default")
      (node (ref "LED7") (pin "1") (pinfunction "A_1") (pintype "passive"))
      (node (ref "R35") (pin "P$1") (pinfunction "1_P$1") (pintype "passive"))
    )
    (net (code "50") (name "Net-(LED7-C)") (class "Default")
      (node (ref "J18") (pin "2") (pinfunction "2_2") (pintype "passive"))
      (node (ref "LED7") (pin "2") (pinfunction "C_2") (pintype "passive"))
      (node (ref "U26") (pin "3") (pinfunction "C(3)_3") (pintype "input"))
    )
    (net (code "51") (name "Net-(LED9-A)") (class "Default")
      (node (ref "LED9") (pin "1") (pinfunction "A_1") (pintype "passive"))
      (node (ref "R37") (pin "P$1") (pinfunction "1_P$1") (pintype "passive"))
    )
    (net (code "52") (name "Net-(LED10-A)") (class "Default")
      (node (ref "LED10") (pin "1") (pinfunction "A_1") (pintype "passive"))
      (node (ref "R46") (pin "P$1") (pinfunction "1_P$1") (pintype "passive"))
    )
    (net (code "53") (name "Net-(LED13-A)") (class "Default")
      (node (ref "LED13") (pin "1") (pinfunction "A_1") (pintype "passive"))
      (node (ref "R49") (pin "P$1") (pinfunction "1_P$1") (pintype "passive"))
    )
    (net (code "54") (name "Net-(LED14-A)") (class "Default")
      (node (ref "LED14") (pin "1") (pinfunction "A_1") (pintype "passive"))
      (node (ref "R58") (pin "P$1") (pinfunction "1_P$1") (pintype "passive"))
    )
    (net (code "55") (name "Net-(R7-2)") (class "Default")
      (node (ref "R7") (pin "P$2") (pinfunction "2_P$2") (pintype "passive"))
      (node (ref "U6") (pin "1") (pinfunction "B(2)_1") (pintype "input"))
    )
    (net (code "56") (name "Net-(R8-2)") (class "Default")
      (node (ref "R8") (pin "P$2") (pinfunction "2_P$2") (pintype "passive"))
      (node (ref "U7") (pin "1") (pinfunction "B(2)_1") (pintype "input"))
    )
    (net (code "57") (name "Net-(R14-2)") (class "Default")
      (node (ref "R14") (pin "P$2") (pinfunction "2_P$2") (pintype "passive"))
      (node (ref "U8") (pin "1") (pinfunction "B(2)_1") (pintype "input"))
    )
    (net (code "58") (name "Net-(R15-2)") (class "Default")
      (node (ref "R15") (pin "P$2") (pinfunction "2_P$2") (pintype "passive"))
      (node (ref "U13") (pin "1") (pinfunction "B(2)_1") (pintype "input"))
    )
    (net (code "59") (name "Net-(R16-2)") (class "Default")
      (node (ref "R16") (pin "P$2") (pinfunction "2_P$2") (pintype "passive"))
      (node (ref "U14") (pin "1") (pinfunction "B(2)_1") (pintype "input"))
    )
    (net (code "60") (name "Net-(R17-2)") (class "Default")
      (node (ref "R17") (pin "P$2") (pinfunction "2_P$2") (pintype "passive"))
      (node (ref "U15") (pin "1") (pinfunction "B(2)_1") (pintype "input"))
    )
    (net (code "61") (name "Net-(R18-2)") (class "Default")
      (node (ref "R18") (pin "P$2") (pinfunction "2_P$2") (pintype "passive"))
      (node (ref "U16") (pin "1") (pinfunction "B(2)_1") (pintype "input"))
    )
    (net (code "62") (name "Net-(R21-2)") (class "Default")
      (node (ref "R21") (pin "P$2") (pinfunction "2_P$2") (pintype "passive"))
      (node (ref "U18") (pin "1") (pinfunction "B(2)_1") (pintype "input"))
    )
    (net (code "63") (name "Net-(R22-2)") (class "Default")
      (node (ref "R22") (pin "P$2") (pinfunction "2_P$2") (pintype "passive"))
      (node (ref "U20") (pin "1") (pinfunction "B(2)_1") (pintype "input"))
    )
    (net (code "64") (name "Net-(R26-2)") (class "Default")
      (node (ref "R26") (pin "P$2") (pinfunction "2_P$2") (pintype "passive"))
      (node (ref "U22") (pin "1") (pinfunction "B(2)_1") (pintype "input"))
    )
    (net (code "65") (name "Net-(R30-2)") (class "Default")
      (node (ref "R30") (pin "P$2") (pinfunction "2_P$2") (pintype "passive"))
      (node (ref "U24") (pin "1") (pinfunction "B(2)_1") (pintype "input"))
    )
    (net (code "66") (name "Net-(R34-2)") (class "Default")
      (node (ref "R34") (pin "P$2") (pinfunction "2_P$2") (pintype "passive"))
      (node (ref "U26") (pin "1") (pinfunction "B(2)_1") (pintype "input"))
    )
    (net (code "67") (name "Net-(R36-2)") (class "Default")
      (node (ref "R36") (pin "P$2") (pinfunction "2_P$2") (pintype "passive"))
      (node (ref "U27") (pin "1") (pinfunction "B(2)_1") (pintype "input"))
    )
    (net (code "68") (name "Net-(R45-2)") (class "Default")
      (node (ref "R45") (pin "P$2") (pinfunction "2_P$2") (pintype "passive"))
      (node (ref "U30") (pin "1") (pinfunction "B(2)_1") (pintype "input"))
    )
    (net (code "69") (name "Net-(R48-2)") (class "Default")
      (node (ref "R48") (pin "P$2") (pinfunction "2_P$2") (pintype "passive"))
      (node (ref "U31") (pin "1") (pinfunction "B(2)_1") (pintype "input"))
    )
    (net (code "70") (name "Net-(R57-2)") (class "Default")
      (node (ref "R57") (pin "P$2") (pinfunction "2_P$2") (pintype "passive"))
      (node (ref "U34") (pin "1") (pinfunction "B(2)_1") (pintype "input"))
    )
    (net (code "71") (name "RELAY_1_A1") (class "Default")
      (node (ref "R22") (pin "P$1") (pinfunction "1_P$1") (pintype "passive"))
      (node (ref "U5") (pin "24") (pinfunction "24/P204_24") (pintype "bidirectional"))
    )
    (net (code "72") (name "RELAY_2_A1") (class "Default")
      (node (ref "R26") (pin "P$1") (pinfunction "1_P$1") (pintype "passive"))
      (node (ref "U5") (pin "21") (pinfunction "21/P207_21") (pintype "power_in"))
    )
    (net (code "73") (name "RELAY_3_A1") (class "Default")
      (node (ref "R30") (pin "P$1") (pinfunction "1_P$1") (pintype "passive"))
      (node (ref "U5") (pin "22") (pinfunction "22/P206_22") (pintype "bidirectional"))
    )
    (net (code "74") (name "RELAY_4_A1") (class "Default")
      (node (ref "R34") (pin "P$1") (pinfunction "1_P$1") (pintype "passive"))
      (node (ref "U5") (pin "31") (pinfunction "31/P301_31") (pintype "bidirectional"))
    )
    (net (code "75") (name "RESET_A1") (class "Default")
      (node (ref "C28") (pin "P$1") (pinfunction "1_P$1") (pintype "passive"))
      (node (ref "J28") (pin "2") (pinfunction "2_2") (pintype "passive"))
      (node (ref "R62") (pin "P$1") (pinfunction "1_P$1") (pintype "passive"))
      (node (ref "U5") (pin "25") (pinfunction "25/RES_25") (pintype "input"))
    )
    (net (code "76") (name "SCLK") (class "Default")
      (node (ref "J29") (pin "5") (pinfunction "5_5") (pintype "passive"))
      (node (ref "J29") (pin "6") (pinfunction "6_6") (pintype "passive"))
      (node (ref "U5") (pin "46") (pinfunction "46/P102_46") (pintype "bidirectional"))
    )
    (net (code "77") (name "SSL0_A1") (class "Default")
      (node (ref "J29") (pin "3") (pinfunction "3_3") (pintype "passive"))
      (node (ref "J29") (pin "4") (pinfunction "4_4") (pintype "passive"))
      (node (ref "U5") (pin "45") (pinfunction "45/P103_45") (pintype "bidirectional"))
    )
    (net (code "78") (name "STEP_M0A1") (class "Default")
      (node (ref "R7") (pin "P$1") (pinfunction "1_P$1") (pintype "passive"))
      (node (ref "U5") (pin "16") (pinfunction "16/P407_16") (pintype "bidirectional"))
    )
    (net (code "79") (name "STEP_M1A1") (class "Default")
      (node (ref "R16") (pin "P$1") (pinfunction "1_P$1") (pintype "passive"))
      (node (ref "U5") (pin "12") (pinfunction "12/P411_12") (pintype "bidirectional"))
    )
    (net (code "80") (name "TCK_A1") (class "Default")
      (node (ref "J28") (pin "6") (pinfunction "6_6") (pintype "passive"))
      (node (ref "U5") (pin "32") (pinfunction "32/P300/TCK/SWCLK_32") (pintype "bidirectional"))
    )
    (net (code "81") (name "TDI_A1") (class "Default")
      (node (ref "J28") (pin "3") (pinfunction "3_3") (pintype "passive"))
      (node (ref "U5") (pin "35") (pinfunction "35/P110/TDI_35") (pintype "bidirectional"))
    )
    (net (code "82") (name "TDO_A1") (class "Default")
      (node (ref "J28") (pin "4") (pinfunction "4_4") (pintype "passive"))
      (node (ref "U5") (pin "34") (pinfunction "34/P109/TDO/SWO_34") (pintype "bidirectional"))
    )
    (net (code "83") (name "TMS_A1") (class "Default")
      (node (ref "J28") (pin "5") (pinfunction "5_5") (pintype "passive"))
      (node (ref "U5") (pin "33") (pinfunction "33/P108/TMS/SWDIO_33") (pintype "bidirectional"))
    )
    (net (code "84") (name "VBATT_M1A1") (class "Default")
      (node (ref "U5") (pin "4") (pinfunction "4/VBATT_4") (pintype "power_in"))
    )
    (net (code "85") (name "VCL0_A1") (class "Default")
      (node (ref "C22") (pin "P$2") (pinfunction "2_P$2") (pintype "passive"))
      (node (ref "U5") (pin "5") (pinfunction "5/VCL0_5") (pintype "power_in"))
    )
    (net (code "86") (name "VDD") (class "Default")
      (node (ref "C15") (pin "P$1") (pinfunction "1_P$1") (pintype "passive"))
      (node (ref "C19") (pin "P$1") (pinfunction "1_P$1") (pintype "passive"))
      (node (ref "C20") (pin "P$1") (pinfunction "1_P$1") (pintype "passive"))
      (node (ref "C21") (pin "P$1") (pinfunction "1_P$1") (pintype "passive"))
      (node (ref "C23") (pin "P$2") (pinfunction "2_P$2") (pintype "passive"))
      (node (ref "C24") (pin "P$1") (pinfunction "1_P$1") (pintype "passive"))
      (node (ref "C25") (pin "P$1") (pinfunction "1_P$1") (pintype "passive"))
      (node (ref "C26") (pin "P$1") (pinfunction "1_P$1") (pintype "passive"))
      (node (ref "C27") (pin "P$1") (pinfunction "1_P$1") (pintype "passive"))
      (node (ref "J1") (pin "P$2") (pinfunction "P$2_P$2") (pintype "bidirectional"))
      (node (ref "R60") (pin "P$1") (pinfunction "1_P$1") (pintype "passive"))
      (node (ref "R61") (pin "P$1") (pinfunction "1_P$1") (pintype "passive"))
      (node (ref "R62") (pin "P$2") (pinfunction "2_P$2") (pintype "passive"))
      (node (ref "U13") (pin "3") (pinfunction "C(3)_3") (pintype "input"))
      (node (ref "U18") (pin "3") (pinfunction "C(3)_3") (pintype "input"))
      (node (ref "U27") (pin "3") (pinfunction "C(3)_3") (pintype "input"))
      (node (ref "U30") (pin "3") (pinfunction "C(3)_3") (pintype "input"))
      (node (ref "U31") (pin "3") (pinfunction "C(3)_3") (pintype "input"))
      (node (ref "U34") (pin "3") (pinfunction "C(3)_3") (pintype "input"))
      (node (ref "U5") (pin "11") (pinfunction "11/VCC_11") (pintype "power_in"))
      (node (ref "U5") (pin "20") (pinfunction "20/VCC_USB_20") (pintype "power_in"))
      (node (ref "U5") (pin "29") (pinfunction "29/VCC_29") (pintype "bidirectional"))
      (node (ref "U5") (pin "38") (pinfunction "38/VCC_38") (pintype "bidirectional"))
      (node (ref "U5") (pin "51") (pinfunction "51/VCC_51") (pintype "bidirectional"))
      (node (ref "U5") (pin "56") (pinfunction "56/VREFH_56") (pintype "power_in"))
      (node (ref "U5") (pin "57") (pinfunction "57/AVCC0_57") (pintype "power_in"))
      (node (ref "U5") (pin "60") (pinfunction "60/VREFH0_60") (pintype "bidirectional"))
    )
    (net (code "87") (name "VDD5") (class "Default")
      (node (ref "J1") (pin "P$3") (pinfunction "P$3_P$3") (pintype "bidirectional"))
      (node (ref "J12") (pin "1") (pinfunction "1_1") (pintype "passive"))
      (node (ref "J14") (pin "1") (pinfunction "1_1") (pintype "passive"))
      (node (ref "J15") (pin "1") (pinfunction "1_1") (pintype "passive"))
      (node (ref "J18") (pin "1") (pinfunction "1_1") (pintype "passive"))
      (node (ref "R25") (pin "P$2") (pinfunction "2_P$2") (pintype "passive"))
      (node (ref "R29") (pin "P$2") (pinfunction "2_P$2") (pintype "passive"))
      (node (ref "R33") (pin "P$2") (pinfunction "2_P$2") (pintype "passive"))
      (node (ref "R35") (pin "P$2") (pinfunction "2_P$2") (pintype "passive"))
    )
    (net (code "88") (name "VDD12") (class "Default")
      (node (ref "J1") (pin "P$4") (pinfunction "P$4_P$4") (pintype "bidirectional"))
    )
    (net (code "89") (name "XCIN_A1") (class "Default")
      (node (ref "C2") (pin "P$1") (pinfunction "1_P$1") (pintype "passive"))
      (node (ref "U5") (pin "6") (pinfunction "6/XCIN_6") (pintype "bidirectional"))
      (node (ref "X1") (pin "P$1") (pinfunction "P$1_P$1") (pintype "bidirectional"))
    )
    (net (code "90") (name "XCOUT_A1") (class "Default")
      (node (ref "C12") (pin "P$1") (pinfunction "1_P$1") (pintype "passive"))
      (node (ref "U5") (pin "7") (pinfunction "7/XCOUT_7") (pintype "bidirectional"))
      (node (ref "X1") (pin "P$2") (pinfunction "P$2_P$2") (pintype "bidirectional"))
    )
    (net (code "91") (name "XTAL1_A1") (class "Default")
      (node (ref "C13") (pin "P$1") (pinfunction "1_P$1") (pintype "passive"))
      (node (ref "U5") (pin "9") (pinfunction "9/XTAL_9") (pintype "bidirectional"))
      (node (ref "Y2") (pin "3") (pinfunction "3_3") (pintype "passive"))
    )
    (net (code "92") (name "XTAL2_A1") (class "Default")
      (node (ref "C14") (pin "P$1") (pinfunction "1_P$1") (pintype "passive"))
      (node (ref "U5") (pin "10") (pinfunction "10/EXTAL_10") (pintype "bidirectional"))
      (node (ref "Y2") (pin "1") (pinfunction "1_1") (pintype "passive"))
    )
  )
)
